# Voltage_sensor_UVW.net
KiCad netlist of a schematic drawn in Altium Designer
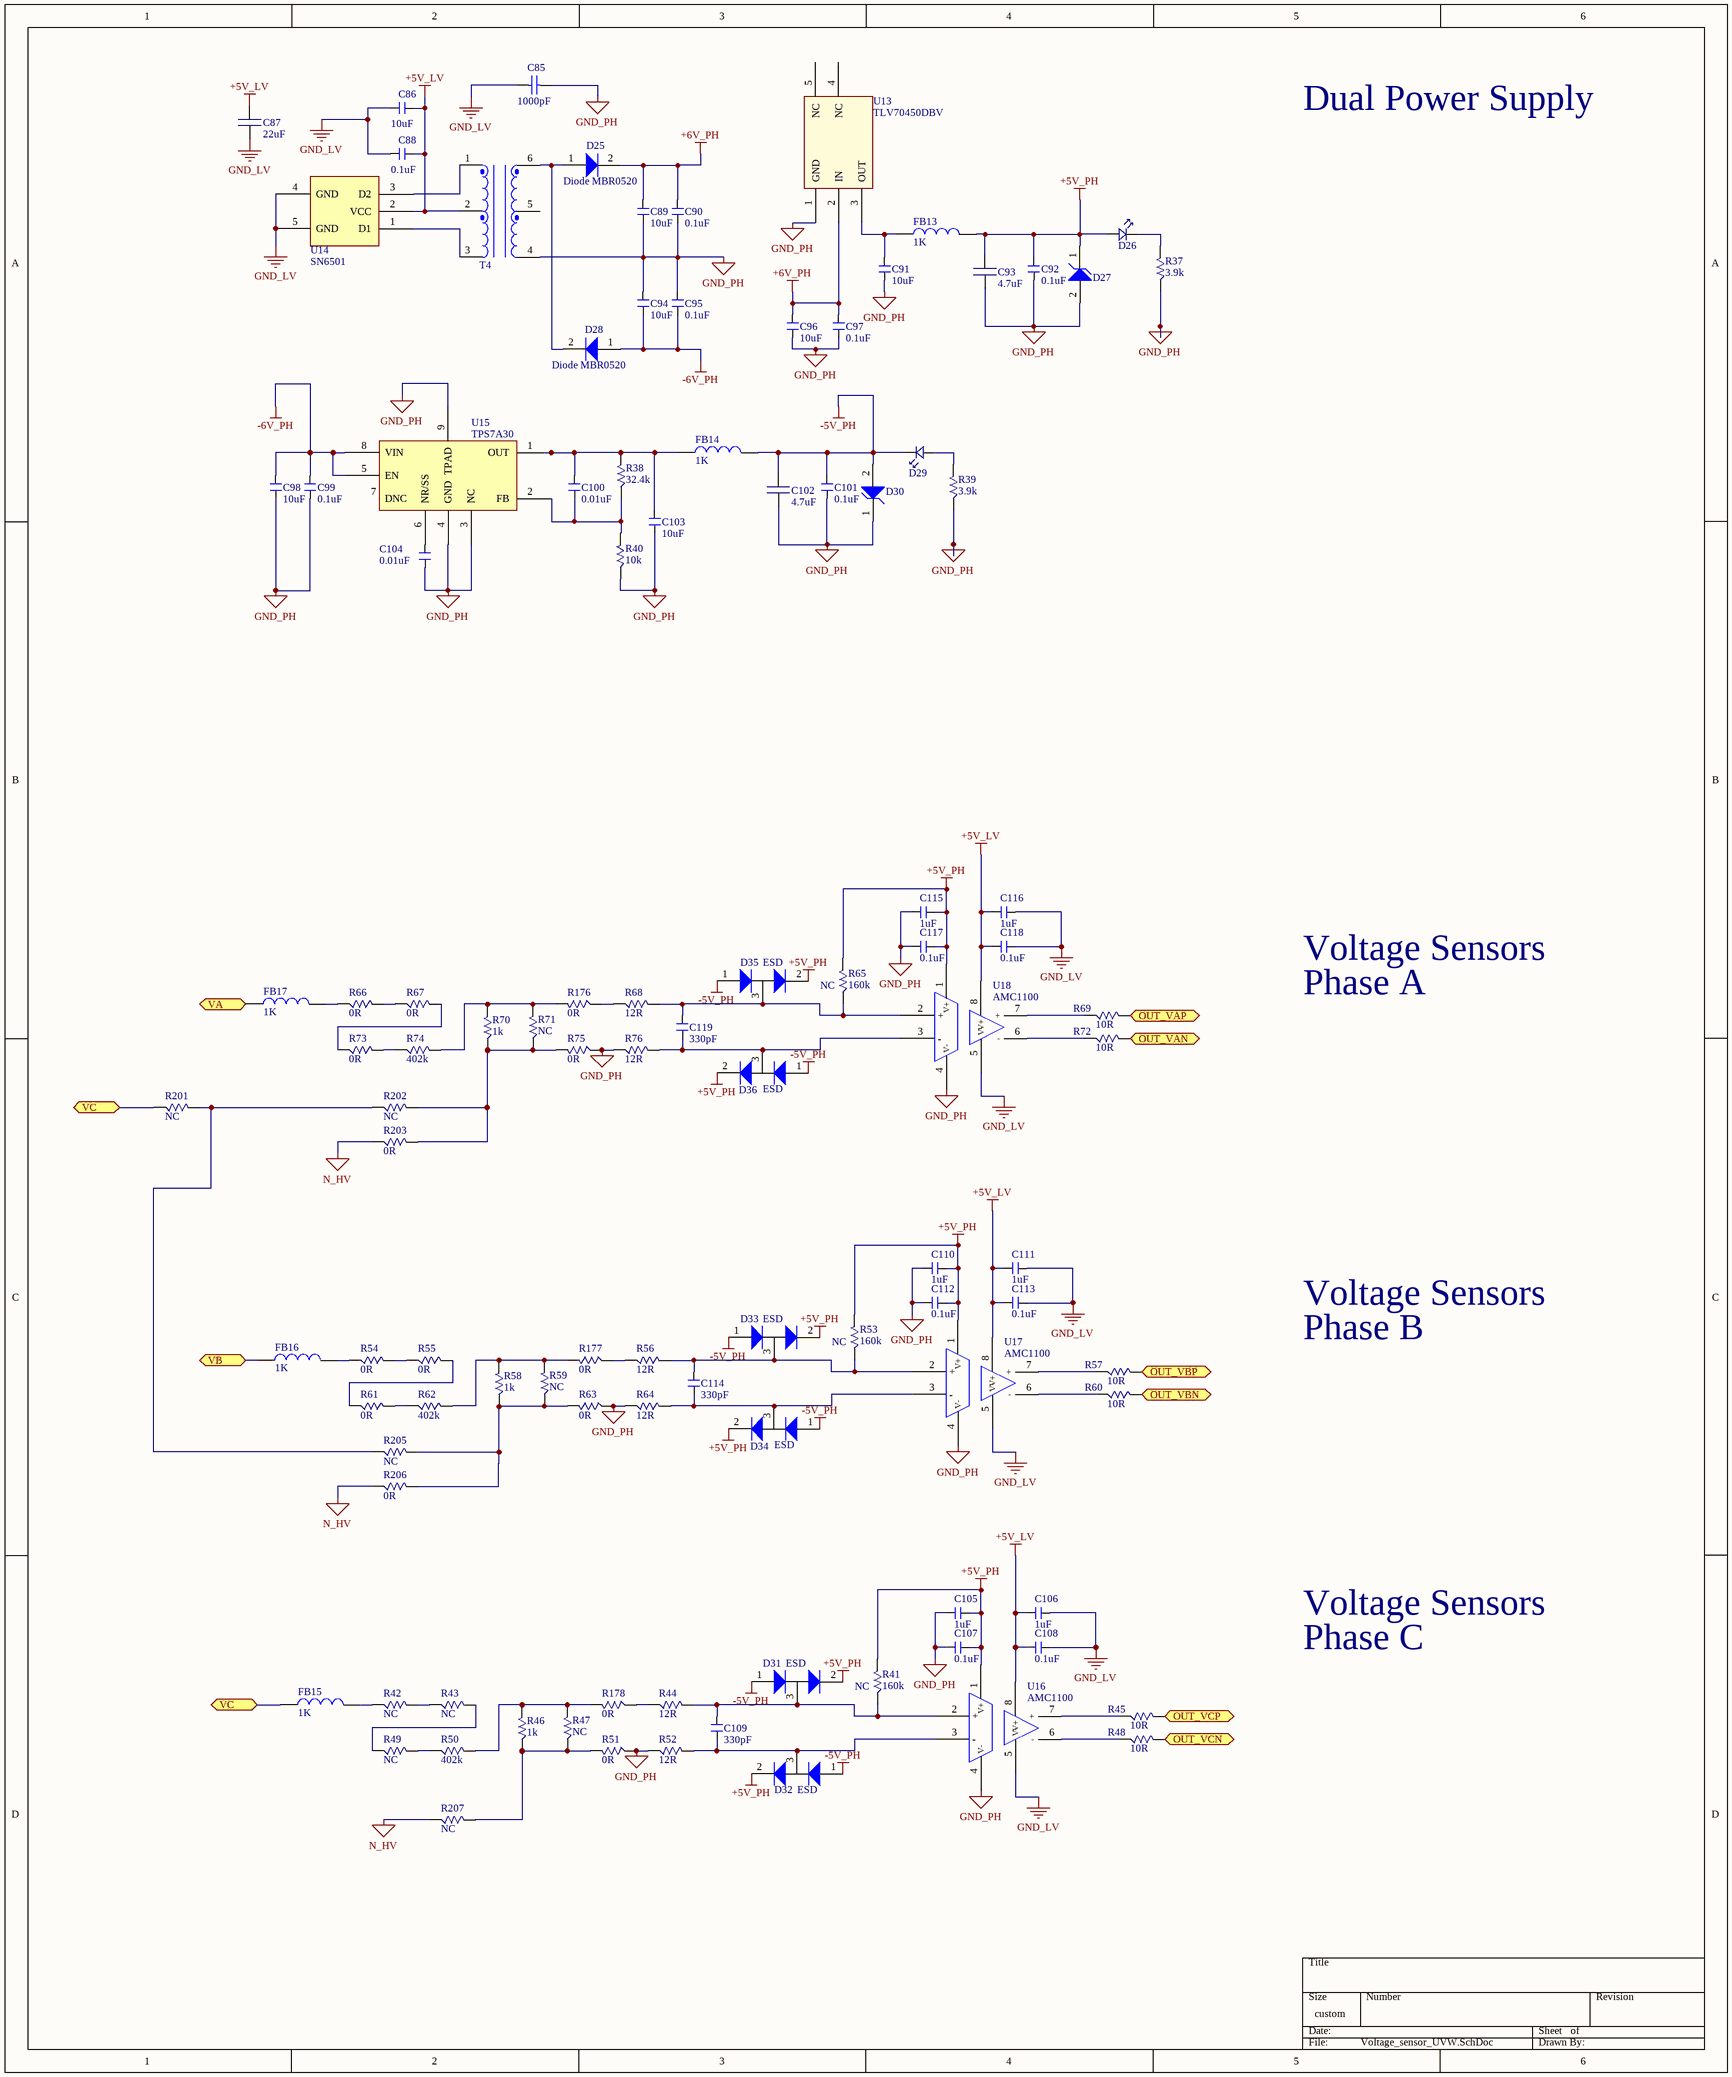
[diagram p0: Voltage_sensor_UVW.SchDoc]

(export (version "E")
  (design (tool "Eeschema 10.0.6"))
  (components
    (comp (ref "C85")
      (value "1000pF")
      (footprint "RAD-0.3")
      (description "CAP CER 1000PF 1KV Y5P RADIAL")
      (fields
        (field (name "PART") "1251PH-ND")
        (field (name "Comment") "Cap TH")
        (field (name "PUBLISHER") "Altium Limited")
      )
      (libsource (lib "Miscellaneous Devices") (part "Cap"))
    )
    (comp (ref "C86")
      (value "10uF")
      (footprint "0603 (1608 Metric)")
      (description "CAP CER 10UF 35V X5R 0805")
      (fields (field (name "PART") "490-10515-1-ND") (field (name "Comment") "Cap 0603_new"))
      (libsource (lib "Library_Microgrid") (part "Cap 0603_new"))
    )
    (comp (ref "C87")
      (value "22uF")
      (footprint "0805 (2012 metric)")
      (description "CAP CER 22UF 35V X5R 0805")
      (fields (field (name "PART") "445-14428-1-ND") (field (name "Comment") "Cap 0805"))
      (libsource (lib "Library_Microgrid") (part "Cap 0805"))
    )
    (comp (ref "C88")
      (value "0.1uF")
      (footprint "0603 (1608 Metric)")
      (description "CAP CER 0.1UF 50V Y5V 0603")
      (fields (field (name "PART") "311-1343-6-ND") (field (name "Comment") "Cap 0603_new"))
      (libsource (lib "Library_Microgrid") (part "Cap 0603_new"))
    )
    (comp (ref "C89")
      (value "10uF")
      (footprint "0603 (1608 Metric)")
      (description "CAP CER 10UF 35V X5R 0805")
      (fields (field (name "PART") "490-10515-1-ND") (field (name "Comment") "Cap 0603_new"))
      (libsource (lib "Library_Microgrid") (part "Cap 0603_new"))
    )
    (comp (ref "C90")
      (value "0.1uF")
      (footprint "0603 (1608 Metric)")
      (description "CAP CER 0.1UF 50V Y5V 0603")
      (fields (field (name "PART") "311-1343-6-ND") (field (name "Comment") "Cap 0603_new"))
      (libsource (lib "Library_Microgrid") (part "Cap 0603_new"))
    )
    (comp (ref "C91")
      (value "10uF")
      (footprint "0603 (1608 Metric)")
      (description "CAP CER 10UF 35V X5R 0805")
      (fields (field (name "PART") "490-10515-1-ND") (field (name "Comment") "Cap 0603_new"))
      (libsource (lib "Library_Microgrid") (part "Cap 0603_new"))
    )
    (comp (ref "C92")
      (value "0.1uF")
      (footprint "0603 (1608 Metric)")
      (description "CAP CER 0.1UF 50V Y5V 0603")
      (fields (field (name "PART") "311-1343-6-ND") (field (name "Comment") "Cap 0603_new"))
      (libsource (lib "Library_Microgrid") (part "Cap 0603_new"))
    )
    (comp (ref "C93")
      (value "4.7uF")
      (footprint "0805 (2012 metric)")
      (description "CAP CER 4.7UF 50V X5R 0805")
      (fields (field (name "PART") "445-5980-1-ND") (field (name "Comment") "Cap 0805"))
      (libsource (lib "Library_Microgrid") (part "Cap 0805"))
    )
    (comp (ref "C94")
      (value "10uF")
      (footprint "0603 (1608 Metric)")
      (description "CAP CER 10UF 35V X5R 0805")
      (fields (field (name "PART") "490-10515-1-ND") (field (name "Comment") "Cap 0603_new"))
      (libsource (lib "Library_Microgrid") (part "Cap 0603_new"))
    )
    (comp (ref "C95")
      (value "0.1uF")
      (footprint "0603 (1608 Metric)")
      (description "CAP CER 0.1UF 50V Y5V 0603")
      (fields (field (name "PART") "311-1343-6-ND") (field (name "Comment") "Cap 0603_new"))
      (libsource (lib "Library_Microgrid") (part "Cap 0603_new"))
    )
    (comp (ref "C96")
      (value "10uF")
      (footprint "0603 (1608 Metric)")
      (description "CAP CER 10UF 35V X5R 0805")
      (fields (field (name "PART") "490-10515-1-ND") (field (name "Comment") "Cap 0603_new"))
      (libsource (lib "Library_Microgrid") (part "Cap 0603_new"))
    )
    (comp (ref "C97")
      (value "0.1uF")
      (footprint "0603 (1608 Metric)")
      (description "CAP CER 0.1UF 50V Y5V 0603")
      (fields (field (name "PART") "311-1343-6-ND") (field (name "Comment") "Cap 0603_new"))
      (libsource (lib "Library_Microgrid") (part "Cap 0603_new"))
    )
    (comp (ref "C98")
      (value "10uF")
      (footprint "0603 (1608 Metric)")
      (description "CAP CER 10UF 35V X5R 0805")
      (fields (field (name "PART") "490-10515-1-ND") (field (name "Comment") "Cap 0603_new"))
      (libsource (lib "Library_Microgrid") (part "Cap 0603_new"))
    )
    (comp (ref "C99")
      (value "0.1uF")
      (footprint "0603 (1608 Metric)")
      (description "CAP CER 0.1UF 50V Y5V 0603")
      (fields (field (name "PART") "311-1343-6-ND") (field (name "Comment") "Cap 0603_new"))
      (libsource (lib "Library_Microgrid") (part "Cap 0603_new"))
    )
    (comp (ref "C100")
      (value "0.01uF")
      (footprint "0603 (1608 Metric)")
      (description "CAP CER 10000PF 100V X7R 0603")
      (fields (field (name "PART") "478-7418-1-ND") (field (name "Comment") "Cap 0603_new"))
      (libsource (lib "Library_Microgrid") (part "Cap 0603_new"))
    )
    (comp (ref "C101")
      (value "0.1uF")
      (footprint "0603 (1608 Metric)")
      (description "CAP CER 0.1UF 50V Y5V 0603")
      (fields (field (name "PART") "311-1343-6-ND") (field (name "Comment") "Cap 0603_new"))
      (libsource (lib "Library_Microgrid") (part "Cap 0603_new"))
    )
    (comp (ref "C102")
      (value "4.7uF")
      (footprint "0805 (2012 metric)")
      (description "CAP CER 4.7UF 50V X5R 0805")
      (fields (field (name "PART") "445-5980-1-ND") (field (name "Comment") "Cap 0805"))
      (libsource (lib "Library_Microgrid") (part "Cap 0805"))
    )
    (comp (ref "C103")
      (value "10uF")
      (footprint "0603 (1608 Metric)")
      (description "CAP CER 10UF 35V X5R 0805")
      (fields (field (name "PART") "490-10515-1-ND") (field (name "Comment") "Cap 0603_new"))
      (libsource (lib "Library_Microgrid") (part "Cap 0603_new"))
    )
    (comp (ref "C104")
      (value "0.01uF")
      (footprint "0603 (1608 Metric)")
      (description "CAP CER 10000PF 100V X7R 0603")
      (fields (field (name "PART") "478-7418-1-ND") (field (name "Comment") "Cap 0603_new"))
      (libsource (lib "Library_Microgrid") (part "Cap 0603_new"))
    )
    (comp (ref "C105")
      (value "1uF")
      (footprint "0603 (1608 Metric)")
      (description "CAP CER 1UF 50V X5R 0603")
      (fields (field (name "PART") "1276-1860-1-ND") (field (name "Comment") "Cap 0603_new"))
      (libsource (lib "Library_Microgrid") (part "Cap 0603_new"))
    )
    (comp (ref "C106")
      (value "1uF")
      (footprint "0603 (1608 Metric)")
      (description "CAP CER 1UF 50V X5R 0603")
      (fields (field (name "PART") "1276-1860-1-ND") (field (name "Comment") "Cap 0603_new"))
      (libsource (lib "Library_Microgrid") (part "Cap 0603_new"))
    )
    (comp (ref "C107")
      (value "0.1uF")
      (footprint "0603 (1608 Metric)")
      (description "CAP CER 0.1UF 50V Y5V 0603")
      (fields (field (name "PART") "311-1343-6-ND") (field (name "Comment") "Cap 0603_new"))
      (libsource (lib "Library_Microgrid") (part "Cap 0603_new"))
    )
    (comp (ref "C108")
      (value "0.1uF")
      (footprint "0603 (1608 Metric)")
      (description "CAP CER 0.1UF 50V Y5V 0603")
      (fields (field (name "PART") "311-1343-6-ND") (field (name "Comment") "Cap 0603_new"))
      (libsource (lib "Library_Microgrid") (part "Cap 0603_new"))
    )
    (comp (ref "C109")
      (value "330pF")
      (footprint "0603 (1608 Metric)")
      (description "CAP CER 330PF 50V C0G 0603")
      (fields (field (name "PART") "445-7033-2-ND") (field (name "Comment") "Cap 0603_new"))
      (libsource (lib "Library_Microgrid") (part "Cap 0603_new"))
    )
    (comp (ref "C110")
      (value "1uF")
      (footprint "0603 (1608 Metric)")
      (description "CAP CER 1UF 50V X5R 0603")
      (fields (field (name "PART") "1276-1860-1-ND") (field (name "Comment") "Cap 0603_new"))
      (libsource (lib "Library_Microgrid") (part "Cap 0603_new"))
    )
    (comp (ref "C111")
      (value "1uF")
      (footprint "0603 (1608 Metric)")
      (description "CAP CER 1UF 50V X5R 0603")
      (fields (field (name "PART") "1276-1860-1-ND") (field (name "Comment") "Cap 0603_new"))
      (libsource (lib "Library_Microgrid") (part "Cap 0603_new"))
    )
    (comp (ref "C112")
      (value "0.1uF")
      (footprint "0603 (1608 Metric)")
      (description "CAP CER 0.1UF 50V Y5V 0603")
      (fields (field (name "PART") "311-1343-6-ND") (field (name "Comment") "Cap 0603_new"))
      (libsource (lib "Library_Microgrid") (part "Cap 0603_new"))
    )
    (comp (ref "C113")
      (value "0.1uF")
      (footprint "0603 (1608 Metric)")
      (description "CAP CER 0.1UF 50V Y5V 0603")
      (fields (field (name "PART") "311-1343-6-ND") (field (name "Comment") "Cap 0603_new"))
      (libsource (lib "Library_Microgrid") (part "Cap 0603_new"))
    )
    (comp (ref "C114")
      (value "330pF")
      (footprint "0603 (1608 Metric)")
      (description "CAP CER 330PF 50V C0G 0603")
      (fields (field (name "PART") "445-7033-2-ND") (field (name "Comment") "Cap 0603_new"))
      (libsource (lib "Library_Microgrid") (part "Cap 0603_new"))
    )
    (comp (ref "C115")
      (value "1uF")
      (footprint "0603 (1608 Metric)")
      (description "CAP CER 1UF 50V X5R 0603")
      (fields (field (name "PART") "1276-1860-1-ND") (field (name "Comment") "Cap 0603_new"))
      (libsource (lib "Library_Microgrid") (part "Cap 0603_new"))
    )
    (comp (ref "C116")
      (value "1uF")
      (footprint "0603 (1608 Metric)")
      (description "CAP CER 1UF 50V X5R 0603")
      (fields (field (name "PART") "1276-1860-1-ND") (field (name "Comment") "Cap 0603_new"))
      (libsource (lib "Library_Microgrid") (part "Cap 0603_new"))
    )
    (comp (ref "C117")
      (value "0.1uF")
      (footprint "0603 (1608 Metric)")
      (description "CAP CER 0.1UF 50V Y5V 0603")
      (fields (field (name "PART") "311-1343-6-ND") (field (name "Comment") "Cap 0603_new"))
      (libsource (lib "Library_Microgrid") (part "Cap 0603_new"))
    )
    (comp (ref "C118")
      (value "0.1uF")
      (footprint "0603 (1608 Metric)")
      (description "CAP CER 0.1UF 50V Y5V 0603")
      (fields (field (name "PART") "311-1343-6-ND") (field (name "Comment") "Cap 0603_new"))
      (libsource (lib "Library_Microgrid") (part "Cap 0603_new"))
    )
    (comp (ref "C119")
      (value "330pF")
      (footprint "0603 (1608 Metric)")
      (description "CAP CER 330PF 50V C0G 0603")
      (fields (field (name "PART") "445-7033-2-ND") (field (name "Comment") "Cap 0603_new"))
      (libsource (lib "Library_Microgrid") (part "Cap 0603_new"))
    )
    (comp (ref "D25")
      (value "Diode MBR0520")
      (footprint "SOD-123")
      (description "DIODE SCHOTTKY 20V 500MA SOD123")
      (fields (field (name "PART") "MBR0520LT1GOSCT-ND"))
      (libsource (lib "Library_Microgrid") (part "Diode MBR0520"))
    )
    (comp (ref "D26")
      (value "LED")
      (footprint "0805 (2012 Metric) Diode")
      (description "LED 0805")
      (libsource (lib "Library_Microgrid") (part "LED"))
    )
    (comp (ref "D27")
      (value "Diode Zener POWERDI123")
      (footprint "POWERDI")
      (description "DIODE ZENER POWERDI123")
      (fields (field (name "PART") "DFLZ6V2DICT-ND"))
      (libsource (lib "Library_Microgrid") (part "Diode Zener POWERDI123"))
    )
    (comp (ref "D28")
      (value "Diode MBR0520")
      (footprint "SOD-123")
      (description "DIODE SCHOTTKY 20V 500MA SOD123")
      (fields (field (name "PART") "MBR0520LT1GOSCT-ND"))
      (libsource (lib "Library_Microgrid") (part "Diode MBR0520"))
    )
    (comp (ref "D29")
      (value "LED")
      (footprint "0805 (2012 Metric) Diode")
      (description "LED 0805")
      (libsource (lib "Library_Microgrid") (part "LED"))
    )
    (comp (ref "D30")
      (value "Diode Zener POWERDI123")
      (footprint "POWERDI")
      (description "DIODE ZENER POWERDI123")
      (fields (field (name "PART") "DFLZ6V2DICT-ND"))
      (libsource (lib "Library_Microgrid") (part "Diode Zener POWERDI123"))
    )
    (comp (ref "D31")
      (value "ESD")
      (footprint "SOT323_ESD")
      (description "TVS DIODE")
      (fields (field (name "PART") "ESD1P0RFWH6327XTSA1CT") (field (name "Comment") "TVS - Diodes"))
      (libsource (lib "Library_Microgrid") (part "Diode_ESD"))
    )
    (comp (ref "D32")
      (value "ESD")
      (footprint "SOT323_ESD")
      (description "TVS DIODE")
      (fields (field (name "PART") "ESD1P0RFWH6327XTSA1CT") (field (name "Comment") "TVS - Diodes"))
      (libsource (lib "Library_Microgrid") (part "Diode_ESD"))
    )
    (comp (ref "D33")
      (value "ESD")
      (footprint "SOT323_ESD")
      (description "TVS DIODE")
      (fields (field (name "PART") "ESD1P0RFWH6327XTSA1CT") (field (name "Comment") "TVS - Diodes"))
      (libsource (lib "Library_Microgrid") (part "Diode_ESD"))
    )
    (comp (ref "D34")
      (value "ESD")
      (footprint "SOT323_ESD")
      (description "TVS DIODE")
      (fields (field (name "PART") "ESD1P0RFWH6327XTSA1CT") (field (name "Comment") "TVS - Diodes"))
      (libsource (lib "Library_Microgrid") (part "Diode_ESD"))
    )
    (comp (ref "D35")
      (value "ESD")
      (footprint "SOT323_ESD")
      (description "TVS DIODE")
      (fields (field (name "PART") "ESD1P0RFWH6327XTSA1CT") (field (name "Comment") "TVS - Diodes"))
      (libsource (lib "Library_Microgrid") (part "Diode_ESD"))
    )
    (comp (ref "D36")
      (value "ESD")
      (footprint "SOT323_ESD")
      (description "TVS DIODE")
      (fields (field (name "PART") "ESD1P0RFWH6327XTSA1CT") (field (name "Comment") "TVS - Diodes"))
      (libsource (lib "Library_Microgrid") (part "Diode_ESD"))
    )
    (comp (ref "FB13")
      (value "1K")
      (footprint "0603 (1608 Metric)")
      (description "FERRITE BEAD 1 KOHM 0603 1LN")
      (fields (field (name "PART") "445-8672-1-ND") (field (name "Comment") "Ferrite bead"))
      (libsource (lib "Library_Microgrid") (part "Ferrite bead"))
    )
    (comp (ref "FB14")
      (value "1K")
      (footprint "0603 (1608 Metric)")
      (description "FERRITE BEAD 1 KOHM 0603 1LN")
      (fields (field (name "PART") "445-8672-1-ND") (field (name "Comment") "Ferrite bead"))
      (libsource (lib "Library_Microgrid") (part "Ferrite bead"))
    )
    (comp (ref "FB15")
      (value "1K")
      (footprint "0603 (1608 Metric)")
      (description "FERRITE BEAD 1 KOHM 0603 1LN")
      (fields (field (name "PART") "445-8672-1-ND") (field (name "Comment") "Ferrite bead"))
      (libsource (lib "Library_Microgrid") (part "Ferrite bead"))
    )
    (comp (ref "FB16")
      (value "1K")
      (footprint "0603 (1608 Metric)")
      (description "FERRITE BEAD 1 KOHM 0603 1LN")
      (fields (field (name "PART") "445-8672-1-ND") (field (name "Comment") "Ferrite bead"))
      (libsource (lib "Library_Microgrid") (part "Ferrite bead"))
    )
    (comp (ref "FB17")
      (value "1K")
      (footprint "0603 (1608 Metric)")
      (description "FERRITE BEAD 1 KOHM 0603 1LN")
      (fields (field (name "PART") "445-8672-1-ND") (field (name "Comment") "Ferrite bead"))
      (libsource (lib "Library_Microgrid") (part "Ferrite bead"))
    )
    (comp (ref "R37")
      (value "3.9k")
      (footprint "0603 (1608 Metric)")
      (description "RES SMD 3.9K OHM 5% 1/10W 0603")
      (fields (field (name "PART") "541-3.9KGCT-ND") (field (name "Comment") "Resistor 0603"))
      (libsource (lib "Library_Microgrid") (part "Resistor 0603"))
    )
    (comp (ref "R38")
      (value "32.4k")
      (footprint "0603 (1608 Metric)")
      (description "RES SMD 32.4KOHM 0.5% 1/10W 0603")
      (fields (field (name "PART") "311-32.4KDCT-ND") (field (name "Comment") "Resistor 0603"))
      (libsource (lib "Library_Microgrid") (part "Resistor 0603"))
    )
    (comp (ref "R39")
      (value "3.9k")
      (footprint "0603 (1608 Metric)")
      (description "RES SMD 3.9K OHM 5% 1/10W 0603")
      (fields (field (name "PART") "541-3.9KGCT-ND") (field (name "Comment") "Resistor 0603"))
      (libsource (lib "Library_Microgrid") (part "Resistor 0603"))
    )
    (comp (ref "R40")
      (value "10k")
      (footprint "0603 (1608 Metric)")
      (description "RES SMD 10K OHM 0.5% 1/16W 0603")
      (fields (field (name "PART") "RR08P10.0KDCT-ND") (field (name "Comment") "Resistor 0603"))
      (libsource (lib "Library_Microgrid") (part "Resistor 0603"))
    )
    (comp (ref "R41")
      (value "NC")
      (footprint "0603 (1608 Metric)")
      (description "Resistor 0603")
      (fields (field (name "ALTIUM_VALUE") "160k"))
      (libsource (lib "Library_Microgrid") (part "Resistor 0603"))
    )
    (comp (ref "R42")
      (value "NC")
      (footprint "1206")
      (description "RES SMD 332K OHM 0.1% 1/4W 1206")
      (fields (field (name "PART") "RG32P332KBCT-ND") (field (name "Comment") "Resistor 1206"))
      (libsource (lib "Library_Microgrid") (part "Resistor 1206"))
    )
    (comp (ref "R43")
      (value "NC")
      (footprint "1206")
      (description "RES SMD 332K OHM 0.1% 1/4W 1206")
      (fields (field (name "PART") "RG32P332KBCT-ND") (field (name "Comment") "Resistor 1206"))
      (libsource (lib "Library_Microgrid") (part "Resistor 1206"))
    )
    (comp (ref "R44")
      (value "12R")
      (footprint "1206")
      (description "12 Ohm ±0.5% 0.25W, 1/4W Chip Resistor 1206")
      (fields (field (name "PART") "311-2961-1-ND") (field (name "Comment") "Resistor 1206"))
      (libsource (lib "Library_Microgrid") (part "Resistor 1206"))
    )
    (comp (ref "R45")
      (value "10R")
      (footprint "0603 (1608 Metric)")
      (description "RES SMD 10 OHM 0.05% 1/10W 0603")
      (fields (field (name "PART") "RNCF0603AKT10R0CT-ND") (field (name "Comment") "Resistor 0603"))
      (libsource (lib "Library_Microgrid") (part "Resistor 0603"))
    )
    (comp (ref "R46")
      (value "1k")
      (footprint "1206")
      (description "RES SMD 1K OHM 0.1% 1/4W 1206")
      (fields (field (name "PART") "P1.0KBCCT-ND") (field (name "Comment") "Resistor 1206"))
      (libsource (lib "Library_Microgrid") (part "Resistor 1206"))
    )
    (comp (ref "R47")
      (value "NC")
      (footprint "1206")
      (description "Resistor 1206")
      (libsource (lib "Library_Microgrid") (part "Resistor 1206"))
    )
    (comp (ref "R48")
      (value "10R")
      (footprint "0603 (1608 Metric)")
      (description "RES SMD 10 OHM 0.05% 1/10W 0603")
      (fields (field (name "PART") "RNCF0603AKT10R0CT-ND") (field (name "Comment") "Resistor 0603"))
      (libsource (lib "Library_Microgrid") (part "Resistor 0603"))
    )
    (comp (ref "R49")
      (value "NC")
      (footprint "1206")
      (description "RES SMD 332K OHM 0.1% 1/4W 1206")
      (fields (field (name "PART") "RG32P332KBCT-ND") (field (name "Comment") "Resistor 1206"))
      (libsource (lib "Library_Microgrid") (part "Resistor 1206"))
    )
    (comp (ref "R50")
      (value "402k")
      (footprint "1206")
      (description "RES SMD 402K OHM 0.1% 1/4W 1206")
      (fields (field (name "PART") "P402KBCCT-ND") (field (name "Comment") "Resistor 1206"))
      (libsource (lib "Library_Microgrid") (part "Resistor 1206"))
    )
    (comp (ref "R51")
      (value "0R")
      (footprint "0603 (1608 Metric)")
      (fields (field (name "Comment") "Resistor 0603"))
      (libsource (lib "Library_Microgrid") (part "Resistor 0603"))
    )
    (comp (ref "R52")
      (value "12R")
      (footprint "1206")
      (description "12 Ohm ±0.5% 0.25W, 1/4W Chip Resistor 1206")
      (fields (field (name "PART") "311-2961-1-ND") (field (name "Comment") "Resistor 1206"))
      (libsource (lib "Library_Microgrid") (part "Resistor 1206"))
    )
    (comp (ref "R53")
      (value "NC")
      (footprint "0603 (1608 Metric)")
      (description "Resistor 0603")
      (fields (field (name "ALTIUM_VALUE") "160k"))
      (libsource (lib "Library_Microgrid") (part "Resistor 0603"))
    )
    (comp (ref "R54")
      (value "0R")
      (footprint "1206")
      (fields (field (name "Comment") "Resistor 1206"))
      (libsource (lib "Library_Microgrid") (part "Resistor 1206"))
    )
    (comp (ref "R55")
      (value "0R")
      (footprint "1206")
      (fields (field (name "Comment") "Resistor 1206"))
      (libsource (lib "Library_Microgrid") (part "Resistor 1206"))
    )
    (comp (ref "R56")
      (value "12R")
      (footprint "1206")
      (description "12 Ohm ±0.5% 0.25W, 1/4W Chip Resistor 1206")
      (fields (field (name "PART") "311-2961-1-ND") (field (name "Comment") "Resistor 1206"))
      (libsource (lib "Library_Microgrid") (part "Resistor 1206"))
    )
    (comp (ref "R57")
      (value "10R")
      (footprint "0603 (1608 Metric)")
      (description "RES SMD 10 OHM 0.05% 1/10W 0603")
      (fields (field (name "PART") "RNCF0603AKT10R0CT-ND") (field (name "Comment") "Resistor 0603"))
      (libsource (lib "Library_Microgrid") (part "Resistor 0603"))
    )
    (comp (ref "R58")
      (value "1k")
      (footprint "1206")
      (description "RES SMD 1K OHM 0.1% 1/4W 1206")
      (fields (field (name "PART") "P1.0KBCCT-ND") (field (name "Comment") "Resistor 1206"))
      (libsource (lib "Library_Microgrid") (part "Resistor 1206"))
    )
    (comp (ref "R59")
      (value "NC")
      (footprint "1206")
      (description "Resistor 1206")
      (libsource (lib "Library_Microgrid") (part "Resistor 1206"))
    )
    (comp (ref "R60")
      (value "10R")
      (footprint "0603 (1608 Metric)")
      (description "RES SMD 10 OHM 0.05% 1/10W 0603")
      (fields (field (name "PART") "RNCF0603AKT10R0CT-ND") (field (name "Comment") "Resistor 0603"))
      (libsource (lib "Library_Microgrid") (part "Resistor 0603"))
    )
    (comp (ref "R61")
      (value "0R")
      (footprint "1206")
      (fields (field (name "Comment") "Resistor 1206"))
      (libsource (lib "Library_Microgrid") (part "Resistor 1206"))
    )
    (comp (ref "R62")
      (value "402k")
      (footprint "1206")
      (description "RES SMD 402K OHM 0.1% 1/4W 1206")
      (fields (field (name "PART") "P402KBCCT-ND") (field (name "Comment") "Resistor 1206"))
      (libsource (lib "Library_Microgrid") (part "Resistor 1206"))
    )
    (comp (ref "R63")
      (value "0R")
      (footprint "0603 (1608 Metric)")
      (fields (field (name "Comment") "Resistor 0603"))
      (libsource (lib "Library_Microgrid") (part "Resistor 0603"))
    )
    (comp (ref "R64")
      (value "12R")
      (footprint "1206")
      (description "12 Ohm ±0.5% 0.25W, 1/4W Chip Resistor 1206")
      (fields (field (name "PART") "311-2961-1-ND") (field (name "Comment") "Resistor 1206"))
      (libsource (lib "Library_Microgrid") (part "Resistor 1206"))
    )
    (comp (ref "R65")
      (value "NC")
      (footprint "0603 (1608 Metric)")
      (description "Resistor 0603")
      (fields (field (name "ALTIUM_VALUE") "160k"))
      (libsource (lib "Library_Microgrid") (part "Resistor 0603"))
    )
    (comp (ref "R66")
      (value "0R")
      (footprint "1206")
      (description "NC")
      (fields (field (name "Comment") "Resistor 1206"))
      (libsource (lib "Library_Microgrid") (part "Resistor 1206"))
    )
    (comp (ref "R67")
      (value "0R")
      (footprint "1206")
      (fields (field (name "Comment") "Resistor 1206"))
      (libsource (lib "Library_Microgrid") (part "Resistor 1206"))
    )
    (comp (ref "R68")
      (value "12R")
      (footprint "1206")
      (description "12 Ohm ±0.5% 0.25W, 1/4W Chip Resistor 1206")
      (fields (field (name "PART") "311-2961-1-ND") (field (name "Comment") "Resistor 1206"))
      (libsource (lib "Library_Microgrid") (part "Resistor 1206"))
    )
    (comp (ref "R69")
      (value "10R")
      (footprint "0603 (1608 Metric)")
      (description "RES SMD 10 OHM 0.05% 1/10W 0603")
      (fields (field (name "PART") "RNCF0603AKT10R0CT-ND") (field (name "Comment") "Resistor 0603"))
      (libsource (lib "Library_Microgrid") (part "Resistor 0603"))
    )
    (comp (ref "R70")
      (value "1k")
      (footprint "1206")
      (description "RES SMD 1K OHM 0.1% 1/4W 1206")
      (fields (field (name "PART") "P1.0KBCCT-ND") (field (name "Comment") "Resistor 1206"))
      (libsource (lib "Library_Microgrid") (part "Resistor 1206"))
    )
    (comp (ref "R71")
      (value "NC")
      (footprint "1206")
      (description "Resistor 1206")
      (libsource (lib "Library_Microgrid") (part "Resistor 1206"))
    )
    (comp (ref "R72")
      (value "10R")
      (footprint "0603 (1608 Metric)")
      (description "RES SMD 10 OHM 0.05% 1/10W 0603")
      (fields (field (name "PART") "RNCF0603AKT10R0CT-ND") (field (name "Comment") "Resistor 0603"))
      (libsource (lib "Library_Microgrid") (part "Resistor 0603"))
    )
    (comp (ref "R73")
      (value "0R")
      (footprint "1206")
      (fields (field (name "Comment") "Resistor 1206"))
      (libsource (lib "Library_Microgrid") (part "Resistor 1206"))
    )
    (comp (ref "R74")
      (value "402k")
      (footprint "1206")
      (description "RES SMD 402K OHM 0.1% 1/4W 1206")
      (fields (field (name "PART") "P402KBCCT-ND") (field (name "Comment") "Resistor 1206"))
      (libsource (lib "Library_Microgrid") (part "Resistor 1206"))
    )
    (comp (ref "R75")
      (value "0R")
      (footprint "0603 (1608 Metric)")
      (fields (field (name "Comment") "Resistor 0603"))
      (libsource (lib "Library_Microgrid") (part "Resistor 0603"))
    )
    (comp (ref "R76")
      (value "12R")
      (footprint "1206")
      (description "12 Ohm ±0.5% 0.25W, 1/4W Chip Resistor 1206")
      (fields (field (name "PART") "311-2961-1-ND") (field (name "Comment") "Resistor 1206"))
      (libsource (lib "Library_Microgrid") (part "Resistor 1206"))
    )
    (comp (ref "R176")
      (value "0R")
      (footprint "0603 (1608 Metric)")
      (fields (field (name "Comment") "Resistor 0603"))
      (libsource (lib "Library_Microgrid") (part "Resistor 0603"))
    )
    (comp (ref "R177")
      (value "0R")
      (footprint "0603 (1608 Metric)")
      (fields (field (name "Comment") "Resistor 0603"))
      (libsource (lib "Library_Microgrid") (part "Resistor 0603"))
    )
    (comp (ref "R178")
      (value "0R")
      (footprint "0603 (1608 Metric)")
      (fields (field (name "Comment") "Resistor 0603"))
      (libsource (lib "Library_Microgrid") (part "Resistor 0603"))
    )
    (comp (ref "R201")
      (value "NC")
      (footprint "1206")
      (description "RES SMD 332K OHM 0.1% 1/4W 1206")
      (fields (field (name "PART") "RG32P332KBCT-ND") (field (name "Comment") "Resistor 1206"))
      (libsource (lib "Library_Microgrid") (part "Resistor 1206"))
    )
    (comp (ref "R202")
      (value "NC")
      (footprint "1206")
      (description "RES SMD 332K OHM 0.1% 1/4W 1206")
      (fields (field (name "PART") "RG32P332KBCT-ND") (field (name "Comment") "Resistor 1206"))
      (libsource (lib "Library_Microgrid") (part "Resistor 1206"))
    )
    (comp (ref "R203")
      (value "0R")
      (footprint "1206")
      (fields (field (name "Comment") "Resistor 1206"))
      (libsource (lib "Library_Microgrid") (part "Resistor 1206"))
    )
    (comp (ref "R205")
      (value "NC")
      (footprint "1206")
      (description "RES SMD 332K OHM 0.1% 1/4W 1206")
      (fields (field (name "PART") "RG32P332KBCT-ND") (field (name "Comment") "Resistor 1206"))
      (libsource (lib "Library_Microgrid") (part "Resistor 1206"))
    )
    (comp (ref "R206")
      (value "0R")
      (footprint "1206")
      (fields (field (name "Comment") "Resistor 1206"))
      (libsource (lib "Library_Microgrid") (part "Resistor 1206"))
    )
    (comp (ref "R207")
      (value "NC")
      (footprint "1206")
      (description "RES SMD 332K OHM 0.1% 1/4W 1206")
      (fields (field (name "PART") "RG32P332KBCT-ND") (field (name "Comment") "Resistor 1206"))
      (libsource (lib "Library_Microgrid") (part "Resistor 1206"))
    )
    (comp (ref "T4")
      (value "750313769")
      (footprint "Xmr SN6501")
      (description "TRANSFORMER SMD TR1.7 SN6501")
      (fields (field (name "PART") "1297-1107-1-ND"))
      (libsource (lib "Library_Microgrid") (part "750313769"))
    )
    (comp (ref "U13")
      (value "TLV70450DBV")
      (footprint "SOT23-5")
      (description "IC REG LDO 5V 0.15A SOT23-5")
      (fields (field (name "PART") "296-39287-1-ND"))
      (libsource (lib "Library_Microgrid") (part "TLV70450DBV"))
    )
    (comp (ref "U14")
      (value "SN6501")
      (footprint "SOT23-5")
      (description "IC REG CONV PWR SUPPLIES SOT23-5")
      (fields (field (name "PART") "296-37700-1-ND"))
      (libsource (lib "Library_Microgrid") (part "SN6501"))
    )
    (comp (ref "U15")
      (value "TPS7A30")
      (footprint "8-TSSOP")
      (description "IC REG LDO NEG ADJ 0.2A 8MSOP")
      (fields (field (name "PART") "296-27750-1-ND"))
      (libsource (lib "Library_Microgrid") (part "TPS7A30"))
    )
    (comp (ref "U16")
      (value "AMC1100")
      (footprint "SOIC8")
      (description "IC OPAMP ISOLATION 100KHZ 8SOIC")
      (fields (field (name "PART") "296-38822-5-ND"))
      (libsource (lib "Library_Microgrid") (part "AMC1100"))
    )
    (comp (ref "U17")
      (value "AMC1100")
      (footprint "SOIC8")
      (description "IC OPAMP ISOLATION 100KHZ 8SOIC")
      (fields (field (name "PART") "296-38822-5-ND"))
      (libsource (lib "Library_Microgrid") (part "AMC1100"))
    )
    (comp (ref "U18")
      (value "AMC1100")
      (footprint "SOIC8")
      (description "IC OPAMP ISOLATION 100KHZ 8SOIC")
      (fields (field (name "PART") "296-38822-5-ND"))
      (libsource (lib "Library_Microgrid") (part "AMC1100"))
    )
  )
  (nets
    (net (code "1") (name "+5V_LV") (class "Default")
      (node (ref "C106") (pin "1") (pinfunction "OUT_1") (pintype "passive"))
      (node (ref "C108") (pin "1") (pinfunction "OUT_1") (pintype "passive"))
      (node (ref "C111") (pin "1") (pinfunction "OUT_1") (pintype "passive"))
      (node (ref "C113") (pin "1") (pinfunction "OUT_1") (pintype "passive"))
      (node (ref "C116") (pin "1") (pinfunction "OUT_1") (pintype "passive"))
      (node (ref "C118") (pin "1") (pinfunction "OUT_1") (pintype "passive"))
      (node (ref "C86") (pin "2") (pinfunction "OUT_2") (pintype "passive"))
      (node (ref "C87") (pin "2") (pinfunction "OUT_2") (pintype "passive"))
      (node (ref "C88") (pin "2") (pinfunction "OUT_2") (pintype "passive"))
      (node (ref "T4") (pin "2") (pinfunction "1_2") (pintype "passive"))
      (node (ref "U14") (pin "2") (pinfunction "VCC_2") (pintype "passive"))
      (node (ref "U16") (pin "8") (pinfunction "V+_8") (pintype "passive"))
      (node (ref "U17") (pin "8") (pinfunction "V+_8") (pintype "passive"))
      (node (ref "U18") (pin "8") (pinfunction "V+_8") (pintype "passive"))
    )
    (net (code "2") (name "+5V_PH") (class "Default")
      (node (ref "C105") (pin "2") (pinfunction "OUT_2") (pintype "passive"))
      (node (ref "C107") (pin "2") (pinfunction "OUT_2") (pintype "passive"))
      (node (ref "C110") (pin "2") (pinfunction "OUT_2") (pintype "passive"))
      (node (ref "C112") (pin "2") (pinfunction "OUT_2") (pintype "passive"))
      (node (ref "C115") (pin "2") (pinfunction "OUT_2") (pintype "passive"))
      (node (ref "C117") (pin "2") (pinfunction "OUT_2") (pintype "passive"))
      (node (ref "C92") (pin "2") (pinfunction "OUT_2") (pintype "passive"))
      (node (ref "C93") (pin "2") (pinfunction "OUT_2") (pintype "passive"))
      (node (ref "D26") (pin "A") (pinfunction "A_A") (pintype "passive"))
      (node (ref "D27") (pin "1") (pinfunction "Anode_1") (pintype "passive"))
      (node (ref "D31") (pin "2") (pinfunction "node_2") (pintype "passive"))
      (node (ref "D32") (pin "2") (pinfunction "node_2") (pintype "passive"))
      (node (ref "D33") (pin "2") (pinfunction "node_2") (pintype "passive"))
      (node (ref "D34") (pin "2") (pinfunction "node_2") (pintype "passive"))
      (node (ref "D35") (pin "2") (pinfunction "node_2") (pintype "passive"))
      (node (ref "D36") (pin "2") (pinfunction "node_2") (pintype "passive"))
      (node (ref "FB13") (pin "2") (pinfunction "OUT_2") (pintype "passive"))
      (node (ref "R41") (pin "2") (pinfunction "A_2") (pintype "passive"))
      (node (ref "R53") (pin "2") (pinfunction "A_2") (pintype "passive"))
      (node (ref "R65") (pin "2") (pinfunction "A_2") (pintype "passive"))
      (node (ref "U16") (pin "1") (pinfunction "V+_1") (pintype "passive"))
      (node (ref "U17") (pin "1") (pinfunction "V+_1") (pintype "passive"))
      (node (ref "U18") (pin "1") (pinfunction "V+_1") (pintype "passive"))
    )
    (net (code "3") (name "+6V_PH") (class "Default")
      (node (ref "C89") (pin "2") (pinfunction "OUT_2") (pintype "passive"))
      (node (ref "C90") (pin "2") (pinfunction "OUT_2") (pintype "passive"))
      (node (ref "C96") (pin "2") (pinfunction "OUT_2") (pintype "passive"))
      (node (ref "C97") (pin "2") (pinfunction "OUT_2") (pintype "passive"))
      (node (ref "D25") (pin "2") (pinfunction "Anode_2") (pintype "passive"))
      (node (ref "U13") (pin "2") (pinfunction "IN_2") (pintype "passive"))
    )
    (net (code "4") (name "-5V_PH") (class "Default")
      (node (ref "C101") (pin "2") (pinfunction "OUT_2") (pintype "passive"))
      (node (ref "C102") (pin "2") (pinfunction "OUT_2") (pintype "passive"))
      (node (ref "D29") (pin "K") (pinfunction "K_K") (pintype "passive"))
      (node (ref "D30") (pin "2") (pinfunction "Anode_2") (pintype "passive"))
      (node (ref "D31") (pin "1") (pinfunction "node_1") (pintype "passive"))
      (node (ref "D32") (pin "1") (pinfunction "node_1") (pintype "passive"))
      (node (ref "D33") (pin "1") (pinfunction "node_1") (pintype "passive"))
      (node (ref "D34") (pin "1") (pinfunction "node_1") (pintype "passive"))
      (node (ref "D35") (pin "1") (pinfunction "node_1") (pintype "passive"))
      (node (ref "D36") (pin "1") (pinfunction "node_1") (pintype "passive"))
      (node (ref "FB14") (pin "2") (pinfunction "OUT_2") (pintype "passive"))
    )
    (net (code "5") (name "-6V_PH") (class "Default")
      (node (ref "C94") (pin "1") (pinfunction "OUT_1") (pintype "passive"))
      (node (ref "C95") (pin "1") (pinfunction "OUT_1") (pintype "passive"))
      (node (ref "C98") (pin "2") (pinfunction "OUT_2") (pintype "passive"))
      (node (ref "C99") (pin "2") (pinfunction "OUT_2") (pintype "passive"))
      (node (ref "D28") (pin "1") (pinfunction "Anode_1") (pintype "passive"))
      (node (ref "U15") (pin "5") (pinfunction "EN_5") (pintype "passive"))
      (node (ref "U15") (pin "8") (pinfunction "VIN_8") (pintype "power_in"))
    )
    (net (code "6") (name "/OUT_VAN") (class "Default")
      (node (ref "R72") (pin "2") (pinfunction "A_2") (pintype "passive"))
    )
    (net (code "7") (name "/OUT_VAP") (class "Default")
      (node (ref "R69") (pin "2") (pinfunction "A_2") (pintype "passive"))
    )
    (net (code "8") (name "/OUT_VBN") (class "Default")
      (node (ref "R60") (pin "2") (pinfunction "A_2") (pintype "passive"))
    )
    (net (code "9") (name "/OUT_VBP") (class "Default")
      (node (ref "R57") (pin "2") (pinfunction "A_2") (pintype "passive"))
    )
    (net (code "10") (name "/OUT_VCN") (class "Default")
      (node (ref "R48") (pin "2") (pinfunction "A_2") (pintype "passive"))
    )
    (net (code "11") (name "/OUT_VCP") (class "Default")
      (node (ref "R45") (pin "2") (pinfunction "A_2") (pintype "passive"))
    )
    (net (code "12") (name "/VA") (class "Default")
      (node (ref "FB17") (pin "1") (pinfunction "OUT_1") (pintype "passive"))
    )
    (net (code "13") (name "/VB") (class "Default")
      (node (ref "FB16") (pin "1") (pinfunction "OUT_1") (pintype "passive"))
    )
    (net (code "14") (name "/VC") (class "Default")
      (node (ref "FB15") (pin "1") (pinfunction "OUT_1") (pintype "passive"))
      (node (ref "R201") (pin "1") (pinfunction "A_1") (pintype "passive"))
    )
    (net (code "15") (name "GND_LV") (class "Default")
      (node (ref "C106") (pin "2") (pinfunction "OUT_2") (pintype "passive"))
      (node (ref "C108") (pin "2") (pinfunction "OUT_2") (pintype "passive"))
      (node (ref "C111") (pin "2") (pinfunction "OUT_2") (pintype "passive"))
      (node (ref "C113") (pin "2") (pinfunction "OUT_2") (pintype "passive"))
      (node (ref "C116") (pin "2") (pinfunction "OUT_2") (pintype "passive"))
      (node (ref "C118") (pin "2") (pinfunction "OUT_2") (pintype "passive"))
      (node (ref "C85") (pin "1") (pinfunction "1_1") (pintype "passive"))
      (node (ref "C86") (pin "1") (pinfunction "OUT_1") (pintype "passive"))
      (node (ref "C87") (pin "1") (pinfunction "OUT_1") (pintype "passive"))
      (node (ref "C88") (pin "1") (pinfunction "OUT_1") (pintype "passive"))
      (node (ref "U14") (pin "4") (pinfunction "GND_4") (pintype "passive"))
      (node (ref "U14") (pin "5") (pinfunction "GND_5") (pintype "passive"))
      (node (ref "U16") (pin "5") (pinfunction "V-_5") (pintype "passive"))
      (node (ref "U17") (pin "5") (pinfunction "V-_5") (pintype "passive"))
      (node (ref "U18") (pin "5") (pinfunction "V-_5") (pintype "passive"))
    )
    (net (code "16") (name "GND_PH") (class "Default")
      (node (ref "C101") (pin "1") (pinfunction "OUT_1") (pintype "passive"))
      (node (ref "C102") (pin "1") (pinfunction "OUT_1") (pintype "passive"))
      (node (ref "C103") (pin "1") (pinfunction "OUT_1") (pintype "passive"))
      (node (ref "C104") (pin "1") (pinfunction "OUT_1") (pintype "passive"))
      (node (ref "C105") (pin "1") (pinfunction "OUT_1") (pintype "passive"))
      (node (ref "C107") (pin "1") (pinfunction "OUT_1") (pintype "passive"))
      (node (ref "C110") (pin "1") (pinfunction "OUT_1") (pintype "passive"))
      (node (ref "C112") (pin "1") (pinfunction "OUT_1") (pintype "passive"))
      (node (ref "C115") (pin "1") (pinfunction "OUT_1") (pintype "passive"))
      (node (ref "C117") (pin "1") (pinfunction "OUT_1") (pintype "passive"))
      (node (ref "C85") (pin "2") (pinfunction "2_2") (pintype "passive"))
      (node (ref "C89") (pin "1") (pinfunction "OUT_1") (pintype "passive"))
      (node (ref "C90") (pin "1") (pinfunction "OUT_1") (pintype "passive"))
      (node (ref "C91") (pin "1") (pinfunction "OUT_1") (pintype "passive"))
      (node (ref "C92") (pin "1") (pinfunction "OUT_1") (pintype "passive"))
      (node (ref "C93") (pin "1") (pinfunction "OUT_1") (pintype "passive"))
      (node (ref "C94") (pin "2") (pinfunction "OUT_2") (pintype "passive"))
      (node (ref "C95") (pin "2") (pinfunction "OUT_2") (pintype "passive"))
      (node (ref "C96") (pin "1") (pinfunction "OUT_1") (pintype "passive"))
      (node (ref "C97") (pin "1") (pinfunction "OUT_1") (pintype "passive"))
      (node (ref "C98") (pin "1") (pinfunction "OUT_1") (pintype "passive"))
      (node (ref "C99") (pin "1") (pinfunction "OUT_1") (pintype "passive"))
      (node (ref "D27") (pin "2") (pinfunction "Anode_2") (pintype "passive"))
      (node (ref "D30") (pin "1") (pinfunction "Anode_1") (pintype "passive"))
      (node (ref "R37") (pin "1") (pinfunction "A_1") (pintype "passive"))
      (node (ref "R39") (pin "1") (pinfunction "A_1") (pintype "passive"))
      (node (ref "R40") (pin "1") (pinfunction "A_1") (pintype "passive"))
      (node (ref "R51") (pin "1") (pinfunction "A_1") (pintype "passive"))
      (node (ref "R52") (pin "1") (pinfunction "A_1") (pintype "passive"))
      (node (ref "R63") (pin "1") (pinfunction "A_1") (pintype "passive"))
      (node (ref "R64") (pin "1") (pinfunction "A_1") (pintype "passive"))
      (node (ref "R75") (pin "1") (pinfunction "A_1") (pintype "passive"))
      (node (ref "R76") (pin "1") (pinfunction "A_1") (pintype "passive"))
      (node (ref "T4") (pin "4") (pinfunction "1_4") (pintype "passive"))
      (node (ref "U13") (pin "1") (pinfunction "GND_1") (pintype "passive"))
      (node (ref "U15") (pin "3") (pinfunction "NC_3") (pintype "passive"))
      (node (ref "U15") (pin "4") (pinfunction "GND_4") (pintype "power_in"))
      (node (ref "U15") (pin "9") (pinfunction "TPAD_9") (pintype "power_in"))
      (node (ref "U16") (pin "4") (pinfunction "V-_4") (pintype "passive"))
      (node (ref "U17") (pin "4") (pinfunction "V-_4") (pintype "passive"))
      (node (ref "U18") (pin "4") (pinfunction "V-_4") (pintype "passive"))
    )
    (net (code "17") (name "N_HV") (class "Default")
      (node (ref "R203") (pin "1") (pinfunction "A_1") (pintype "passive"))
      (node (ref "R206") (pin "1") (pinfunction "A_1") (pintype "passive"))
      (node (ref "R207") (pin "1") (pinfunction "A_1") (pintype "passive"))
    )
    (net (code "18") (name "Net-(C109-OUT-Pad1)") (class "Default")
      (node (ref "C109") (pin "1") (pinfunction "OUT_1") (pintype "passive"))
      (node (ref "D31") (pin "3") (pinfunction "node_3") (pintype "passive"))
      (node (ref "R41") (pin "1") (pinfunction "A_1") (pintype "passive"))
      (node (ref "R44") (pin "2") (pinfunction "A_2") (pintype "passive"))
      (node (ref "U16") (pin "2") (pinfunction "+_2") (pintype "passive"))
    )
    (net (code "19") (name "Net-(C109-OUT-Pad2)") (class "Default")
      (node (ref "C109") (pin "2") (pinfunction "OUT_2") (pintype "passive"))
      (node (ref "D32") (pin "3") (pinfunction "node_3") (pintype "passive"))
      (node (ref "R52") (pin "2") (pinfunction "A_2") (pintype "passive"))
      (node (ref "U16") (pin "3") (pinfunction "-_3") (pintype "passive"))
    )
    (net (code "20") (name "Net-(C114-OUT-Pad1)") (class "Default")
      (node (ref "C114") (pin "1") (pinfunction "OUT_1") (pintype "passive"))
      (node (ref "D33") (pin "3") (pinfunction "node_3") (pintype "passive"))
      (node (ref "R53") (pin "1") (pinfunction "A_1") (pintype "passive"))
      (node (ref "R56") (pin "2") (pinfunction "A_2") (pintype "passive"))
      (node (ref "U17") (pin "2") (pinfunction "+_2") (pintype "passive"))
    )
    (net (code "21") (name "Net-(C114-OUT-Pad2)") (class "Default")
      (node (ref "C114") (pin "2") (pinfunction "OUT_2") (pintype "passive"))
      (node (ref "D34") (pin "3") (pinfunction "node_3") (pintype "passive"))
      (node (ref "R64") (pin "2") (pinfunction "A_2") (pintype "passive"))
      (node (ref "U17") (pin "3") (pinfunction "-_3") (pintype "passive"))
    )
    (net (code "22") (name "Net-(C119-OUT-Pad1)") (class "Default")
      (node (ref "C119") (pin "1") (pinfunction "OUT_1") (pintype "passive"))
      (node (ref "D35") (pin "3") (pinfunction "node_3") (pintype "passive"))
      (node (ref "R65") (pin "1") (pinfunction "A_1") (pintype "passive"))
      (node (ref "R68") (pin "2") (pinfunction "A_2") (pintype "passive"))
      (node (ref "U18") (pin "2") (pinfunction "+_2") (pintype "passive"))
    )
    (net (code "23") (name "Net-(C119-OUT-Pad2)") (class "Default")
      (node (ref "C119") (pin "2") (pinfunction "OUT_2") (pintype "passive"))
      (node (ref "D36") (pin "3") (pinfunction "node_3") (pintype "passive"))
      (node (ref "R76") (pin "2") (pinfunction "A_2") (pintype "passive"))
      (node (ref "U18") (pin "3") (pinfunction "-_3") (pintype "passive"))
    )
    (net (code "24") (name "Net-(D25-Anode-Pad1)") (class "Default")
      (node (ref "D25") (pin "1") (pinfunction "Anode_1") (pintype "passive"))
      (node (ref "D28") (pin "2") (pinfunction "Anode_2") (pintype "passive"))
      (node (ref "T4") (pin "6") (pinfunction "1_6") (pintype "passive"))
    )
    (net (code "25") (name "Net-(D26-PadK)") (class "Default")
      (node (ref "D26") (pin "K") (pinfunction "K_K") (pintype "passive"))
      (node (ref "R37") (pin "2") (pinfunction "A_2") (pintype "passive"))
    )
    (net (code "26") (name "Net-(D29-PadA)") (class "Default")
      (node (ref "D29") (pin "A") (pinfunction "A_A") (pintype "passive"))
      (node (ref "R39") (pin "2") (pinfunction "A_2") (pintype "passive"))
    )
    (net (code "27") (name "Net-(FB15-OUT-Pad2)") (class "Default")
      (node (ref "FB15") (pin "2") (pinfunction "OUT_2") (pintype "passive"))
      (node (ref "R42") (pin "1") (pinfunction "A_1") (pintype "passive"))
    )
    (net (code "28") (name "Net-(FB16-OUT-Pad2)") (class "Default")
      (node (ref "FB16") (pin "2") (pinfunction "OUT_2") (pintype "passive"))
      (node (ref "R54") (pin "1") (pinfunction "A_1") (pintype "passive"))
    )
    (net (code "29") (name "Net-(FB17-OUT-Pad2)") (class "Default")
      (node (ref "FB17") (pin "2") (pinfunction "OUT_2") (pintype "passive"))
      (node (ref "R66") (pin "1") (pinfunction "A_1") (pintype "passive"))
    )
    (net (code "30") (name "Net-(R42-A-Pad2)") (class "Default")
      (node (ref "R42") (pin "2") (pinfunction "A_2") (pintype "passive"))
      (node (ref "R43") (pin "1") (pinfunction "A_1") (pintype "passive"))
    )
    (net (code "31") (name "Net-(R43-A-Pad2)") (class "Default")
      (node (ref "R43") (pin "2") (pinfunction "A_2") (pintype "passive"))
      (node (ref "R49") (pin "1") (pinfunction "A_1") (pintype "passive"))
    )
    (net (code "32") (name "Net-(R45-A-Pad1)") (class "Default")
      (node (ref "R45") (pin "1") (pinfunction "A_1") (pintype "passive"))
      (node (ref "U16") (pin "7") (pinfunction "+_7") (pintype "passive"))
    )
    (net (code "33") (name "Net-(R48-A-Pad1)") (class "Default")
      (node (ref "R48") (pin "1") (pinfunction "A_1") (pintype "passive"))
      (node (ref "U16") (pin "6") (pinfunction "-_6") (pintype "passive"))
    )
    (net (code "34") (name "Net-(R49-A-Pad2)") (class "Default")
      (node (ref "R49") (pin "2") (pinfunction "A_2") (pintype "passive"))
      (node (ref "R50") (pin "1") (pinfunction "A_1") (pintype "passive"))
    )
    (net (code "35") (name "Net-(R54-A-Pad2)") (class "Default")
      (node (ref "R54") (pin "2") (pinfunction "A_2") (pintype "passive"))
      (node (ref "R55") (pin "1") (pinfunction "A_1") (pintype "passive"))
    )
    (net (code "36") (name "Net-(R55-A-Pad2)") (class "Default")
      (node (ref "R55") (pin "2") (pinfunction "A_2") (pintype "passive"))
      (node (ref "R61") (pin "1") (pinfunction "A_1") (pintype "passive"))
    )
    (net (code "37") (name "Net-(R57-A-Pad1)") (class "Default")
      (node (ref "R57") (pin "1") (pinfunction "A_1") (pintype "passive"))
      (node (ref "U17") (pin "7") (pinfunction "+_7") (pintype "passive"))
    )
    (net (code "38") (name "Net-(R60-A-Pad1)") (class "Default")
      (node (ref "R60") (pin "1") (pinfunction "A_1") (pintype "passive"))
      (node (ref "U17") (pin "6") (pinfunction "-_6") (pintype "passive"))
    )
    (net (code "39") (name "Net-(R61-A-Pad2)") (class "Default")
      (node (ref "R61") (pin "2") (pinfunction "A_2") (pintype "passive"))
      (node (ref "R62") (pin "1") (pinfunction "A_1") (pintype "passive"))
    )
    (net (code "40") (name "Net-(R66-A-Pad2)") (class "Default")
      (node (ref "R66") (pin "2") (pinfunction "A_2") (pintype "passive"))
      (node (ref "R67") (pin "1") (pinfunction "A_1") (pintype "passive"))
    )
    (net (code "41") (name "Net-(R67-A-Pad2)") (class "Default")
      (node (ref "R67") (pin "2") (pinfunction "A_2") (pintype "passive"))
      (node (ref "R73") (pin "1") (pinfunction "A_1") (pintype "passive"))
    )
    (net (code "42") (name "Net-(R69-A-Pad1)") (class "Default")
      (node (ref "R69") (pin "1") (pinfunction "A_1") (pintype "passive"))
      (node (ref "U18") (pin "7") (pinfunction "+_7") (pintype "passive"))
    )
    (net (code "43") (name "Net-(R72-A-Pad1)") (class "Default")
      (node (ref "R72") (pin "1") (pinfunction "A_1") (pintype "passive"))
      (node (ref "U18") (pin "6") (pinfunction "-_6") (pintype "passive"))
    )
    (net (code "44") (name "Net-(R73-A-Pad2)") (class "Default")
      (node (ref "R73") (pin "2") (pinfunction "A_2") (pintype "passive"))
      (node (ref "R74") (pin "1") (pinfunction "A_1") (pintype "passive"))
    )
    (net (code "45") (name "Net-(R176-A-Pad1)") (class "Default")
      (node (ref "R176") (pin "1") (pinfunction "A_1") (pintype "passive"))
      (node (ref "R68") (pin "1") (pinfunction "A_1") (pintype "passive"))
    )
    (net (code "46") (name "Net-(R176-A-Pad2)") (class "Default")
      (node (ref "R176") (pin "2") (pinfunction "A_2") (pintype "passive"))
      (node (ref "R70") (pin "2") (pinfunction "A_2") (pintype "passive"))
      (node (ref "R71") (pin "2") (pinfunction "A_2") (pintype "passive"))
      (node (ref "R74") (pin "2") (pinfunction "A_2") (pintype "passive"))
    )
    (net (code "47") (name "Net-(R177-A-Pad1)") (class "Default")
      (node (ref "R177") (pin "1") (pinfunction "A_1") (pintype "passive"))
      (node (ref "R56") (pin "1") (pinfunction "A_1") (pintype "passive"))
    )
    (net (code "48") (name "Net-(R177-A-Pad2)") (class "Default")
      (node (ref "R177") (pin "2") (pinfunction "A_2") (pintype "passive"))
      (node (ref "R58") (pin "2") (pinfunction "A_2") (pintype "passive"))
      (node (ref "R59") (pin "2") (pinfunction "A_2") (pintype "passive"))
      (node (ref "R62") (pin "2") (pinfunction "A_2") (pintype "passive"))
    )
    (net (code "49") (name "Net-(R178-A-Pad1)") (class "Default")
      (node (ref "R178") (pin "1") (pinfunction "A_1") (pintype "passive"))
      (node (ref "R44") (pin "1") (pinfunction "A_1") (pintype "passive"))
    )
    (net (code "50") (name "Net-(R178-A-Pad2)") (class "Default")
      (node (ref "R178") (pin "2") (pinfunction "A_2") (pintype "passive"))
      (node (ref "R46") (pin "2") (pinfunction "A_2") (pintype "passive"))
      (node (ref "R47") (pin "2") (pinfunction "A_2") (pintype "passive"))
      (node (ref "R50") (pin "2") (pinfunction "A_2") (pintype "passive"))
    )
    (net (code "51") (name "Net-(R201-A-Pad2)") (class "Default")
      (node (ref "R201") (pin "2") (pinfunction "A_2") (pintype "passive"))
      (node (ref "R202") (pin "1") (pinfunction "A_1") (pintype "passive"))
      (node (ref "R205") (pin "1") (pinfunction "A_1") (pintype "passive"))
    )
    (net (code "52") (name "Net-(R202-A-Pad2)") (class "Default")
      (node (ref "R202") (pin "2") (pinfunction "A_2") (pintype "passive"))
      (node (ref "R203") (pin "2") (pinfunction "A_2") (pintype "passive"))
      (node (ref "R70") (pin "1") (pinfunction "A_1") (pintype "passive"))
      (node (ref "R71") (pin "1") (pinfunction "A_1") (pintype "passive"))
      (node (ref "R75") (pin "2") (pinfunction "A_2") (pintype "passive"))
    )
    (net (code "53") (name "Net-(R205-A-Pad2)") (class "Default")
      (node (ref "R205") (pin "2") (pinfunction "A_2") (pintype "passive"))
      (node (ref "R206") (pin "2") (pinfunction "A_2") (pintype "passive"))
      (node (ref "R58") (pin "1") (pinfunction "A_1") (pintype "passive"))
      (node (ref "R59") (pin "1") (pinfunction "A_1") (pintype "passive"))
      (node (ref "R63") (pin "2") (pinfunction "A_2") (pintype "passive"))
    )
    (net (code "54") (name "Net-(R207-A-Pad2)") (class "Default")
      (node (ref "R207") (pin "2") (pinfunction "A_2") (pintype "passive"))
      (node (ref "R46") (pin "1") (pinfunction "A_1") (pintype "passive"))
      (node (ref "R47") (pin "1") (pinfunction "A_1") (pintype "passive"))
      (node (ref "R51") (pin "2") (pinfunction "A_2") (pintype "passive"))
    )
    (net (code "55") (name "Net-(U13-OUT)") (class "Default")
      (node (ref "C91") (pin "2") (pinfunction "OUT_2") (pintype "passive"))
      (node (ref "FB13") (pin "1") (pinfunction "OUT_1") (pintype "passive"))
      (node (ref "U13") (pin "3") (pinfunction "OUT_3") (pintype "passive"))
    )
    (net (code "56") (name "Net-(U14-D1)") (class "Default")
      (node (ref "T4") (pin "3") (pinfunction "1_3") (pintype "passive"))
      (node (ref "U14") (pin "1") (pinfunction "D1_1") (pintype "passive"))
    )
    (net (code "57") (name "Net-(U14-D2)") (class "Default")
      (node (ref "T4") (pin "1") (pinfunction "1_1") (pintype "passive"))
      (node (ref "U14") (pin "3") (pinfunction "D2_3") (pintype "passive"))
    )
    (net (code "58") (name "Net-(U15-FB)") (class "Default")
      (node (ref "C100") (pin "2") (pinfunction "OUT_2") (pintype "passive"))
      (node (ref "R38") (pin "1") (pinfunction "A_1") (pintype "passive"))
      (node (ref "R40") (pin "2") (pinfunction "A_2") (pintype "passive"))
      (node (ref "U15") (pin "2") (pinfunction "FB_2") (pintype "passive"))
    )
    (net (code "59") (name "Net-(U15-NR{slash}SS)") (class "Default")
      (node (ref "C104") (pin "2") (pinfunction "OUT_2") (pintype "passive"))
      (node (ref "U15") (pin "6") (pinfunction "NR/SS_6") (pintype "power_in"))
    )
    (net (code "60") (name "Net-(U15-OUT)") (class "Default")
      (node (ref "C100") (pin "1") (pinfunction "OUT_1") (pintype "passive"))
      (node (ref "C103") (pin "2") (pinfunction "OUT_2") (pintype "passive"))
      (node (ref "FB14") (pin "1") (pinfunction "OUT_1") (pintype "passive"))
      (node (ref "R38") (pin "2") (pinfunction "A_2") (pintype "passive"))
      (node (ref "U15") (pin "1") (pinfunction "OUT_1") (pintype "passive"))
    )
    (net (code "61") (name "unconnected-(T4-1-Pad5)") (class "Default")
      (node (ref "T4") (pin "5") (pinfunction "1_5") (pintype "passive"))
    )
    (net (code "62") (name "unconnected-(U13-NC-Pad4)") (class "Default")
      (node (ref "U13") (pin "4") (pinfunction "NC_4") (pintype "passive"))
    )
    (net (code "63") (name "unconnected-(U13-NC-Pad5)") (class "Default")
      (node (ref "U13") (pin "5") (pinfunction "NC_5") (pintype "passive"))
    )
    (net (code "64") (name "unconnected-(U15-DNC-Pad7)") (class "Default")
      (node (ref "U15") (pin "7") (pinfunction "DNC_7") (pintype "passive"))
    )
  )
)
